# Core.net
KiCad netlist of a schematic drawn in Altium Designer
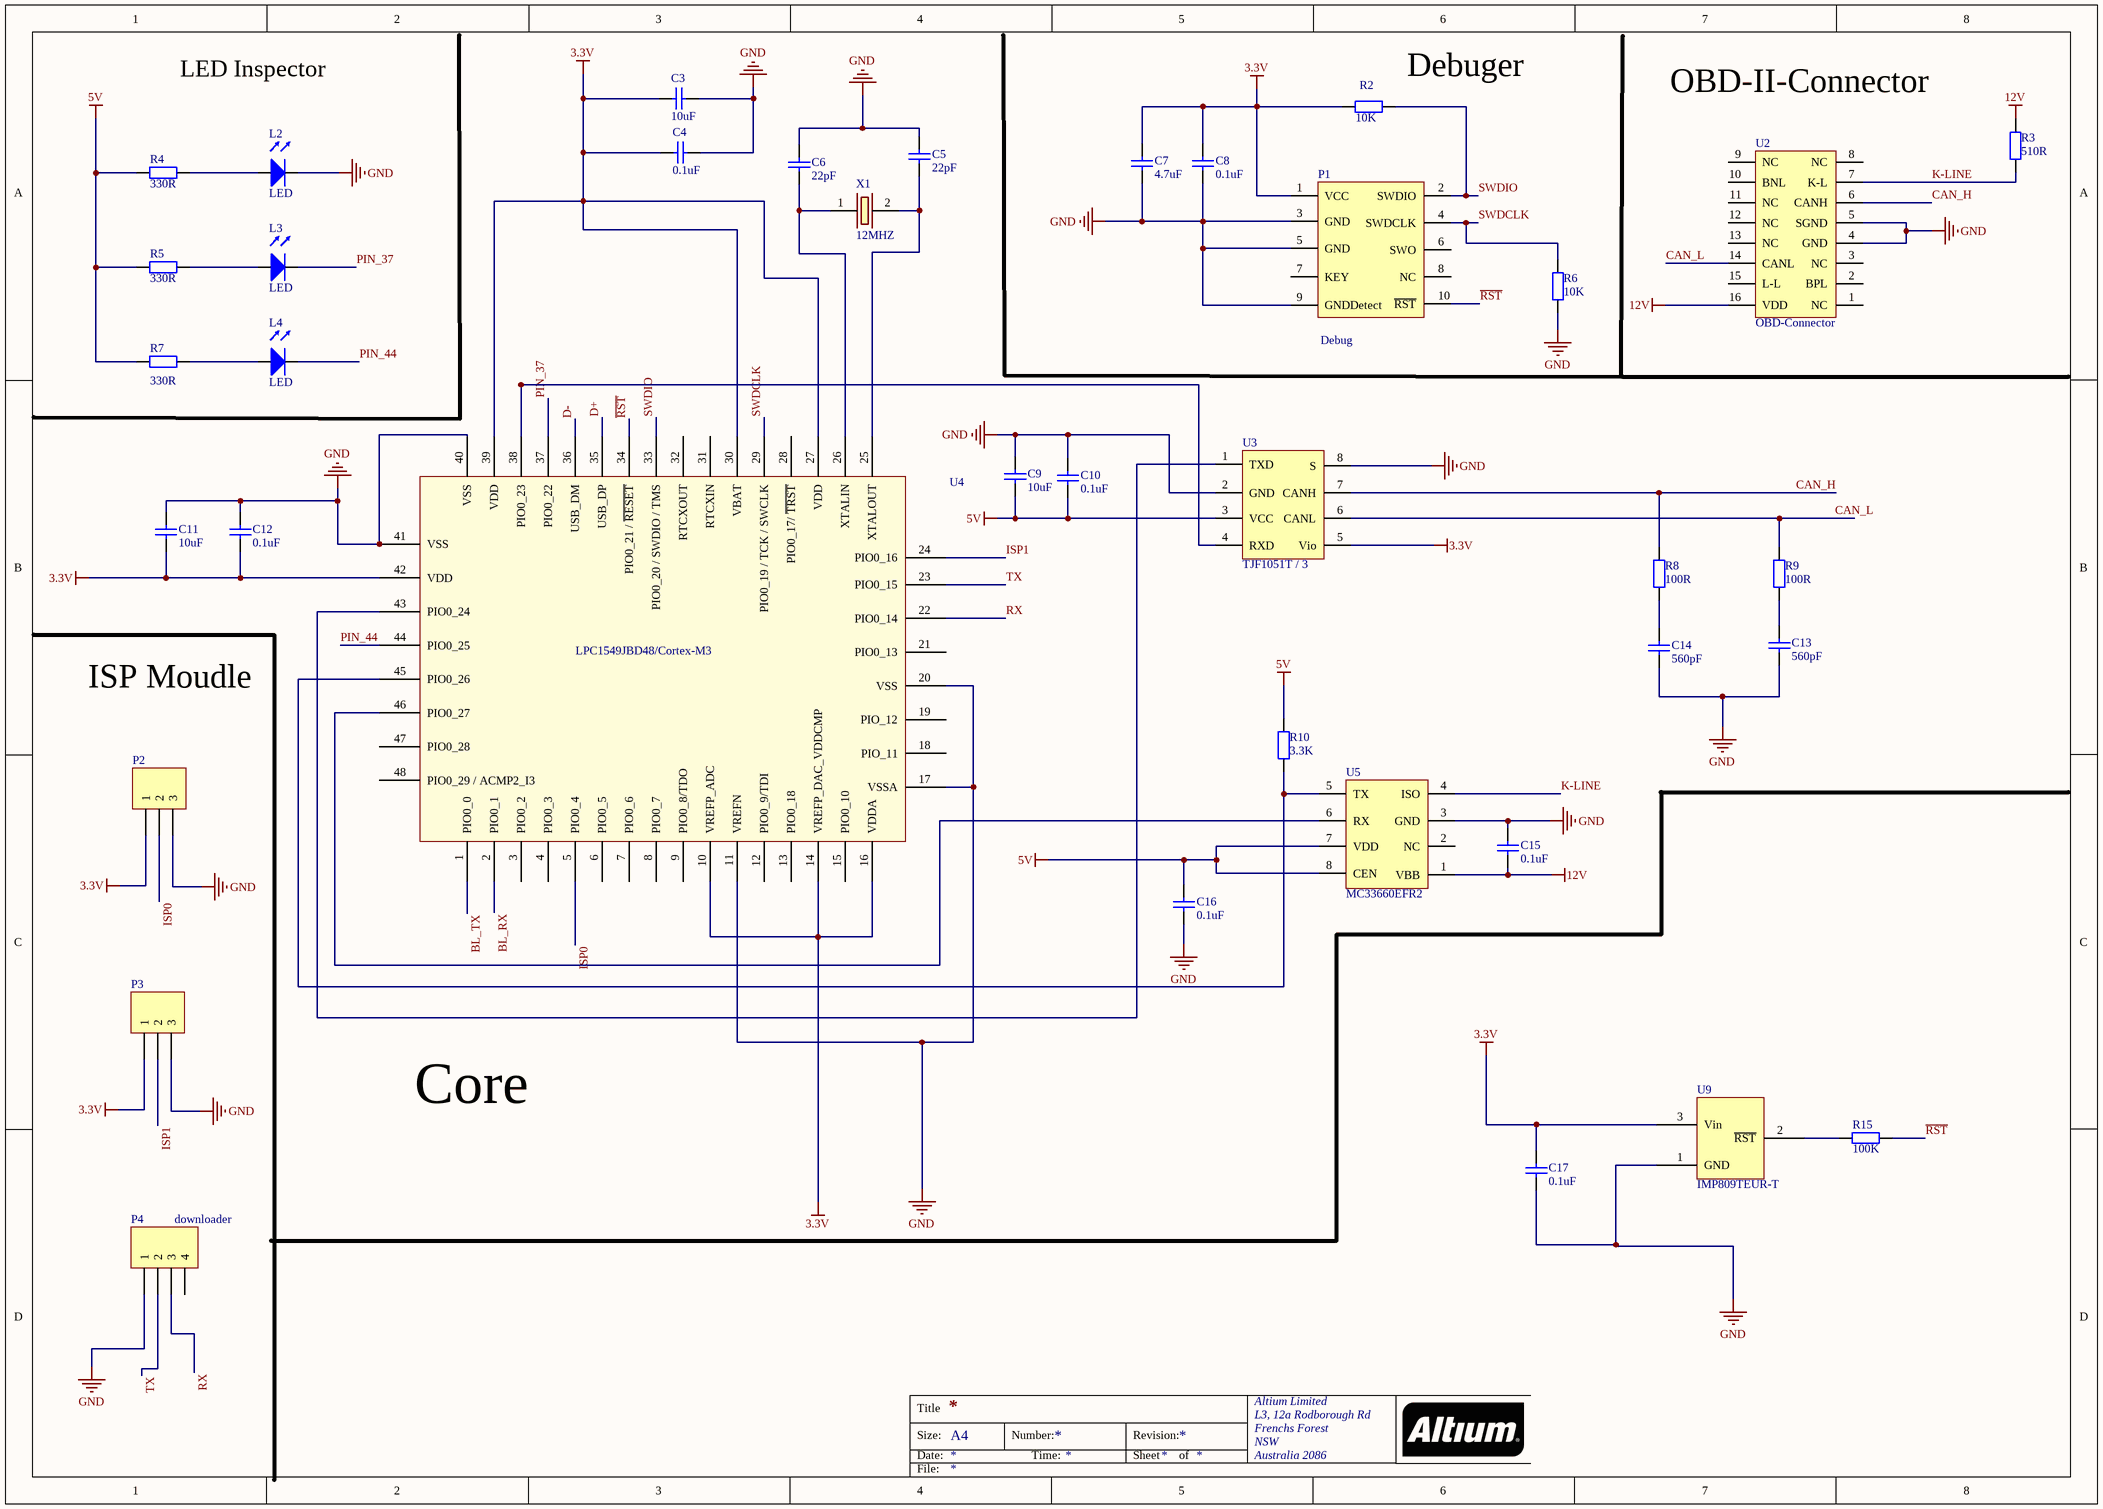
[diagram p0: Core.SchDoc]

(export (version "E")
  (design (tool "Eeschema 10.0.6"))
  (components
    (comp (ref "C3")
      (value "10uF")
      (footprint "0603")
      (description "ceramic")
      (libsource (lib "ToponLib") (part "Cap1"))
    )
    (comp (ref "C4")
      (value "0.1uF")
      (footprint "0603")
      (description "ceramic")
      (libsource (lib "ToponLib") (part "Cap1"))
    )
    (comp (ref "C5")
      (value "22pF")
      (footprint "0603")
      (description "ceramic")
      (libsource (lib "ToponLib") (part "Cap1"))
    )
    (comp (ref "C6")
      (value "22pF")
      (footprint "0603")
      (description "ceramic")
      (libsource (lib "ToponLib") (part "Cap1"))
    )
    (comp (ref "C7")
      (value "4.7uF")
      (footprint "0603")
      (description "ceramic")
      (libsource (lib "ToponLib") (part "Cap1"))
    )
    (comp (ref "C8")
      (value "0.1uF")
      (footprint "0603")
      (description "ceramic")
      (libsource (lib "ToponLib") (part "Cap1"))
    )
    (comp (ref "C9")
      (value "10uF")
      (footprint "0603")
      (description "ceramic")
      (libsource (lib "ToponLib") (part "Cap1"))
    )
    (comp (ref "C10")
      (value "0.1uF")
      (footprint "0603")
      (description "ceramic")
      (libsource (lib "ToponLib") (part "Cap1"))
    )
    (comp (ref "C11")
      (value "10uF")
      (footprint "0603")
      (description "ceramic")
      (libsource (lib "ToponLib") (part "Cap1"))
    )
    (comp (ref "C12")
      (value "0.1uF")
      (footprint "0603")
      (description "ceramic")
      (libsource (lib "ToponLib") (part "Cap1"))
    )
    (comp (ref "C13")
      (value "560pF")
      (footprint "0603")
      (description "ceramic")
      (libsource (lib "ToponLib") (part "Cap1"))
    )
    (comp (ref "C14")
      (value "560pF")
      (footprint "0603")
      (description "ceramic")
      (libsource (lib "ToponLib") (part "Cap1"))
    )
    (comp (ref "C15")
      (value "0.1uF")
      (footprint "0603")
      (description "ceramic")
      (libsource (lib "ToponLib") (part "Cap1"))
    )
    (comp (ref "C16")
      (value "0.1uF")
      (footprint "0603")
      (description "ceramic")
      (libsource (lib "ToponLib") (part "Cap1"))
    )
    (comp (ref "C17")
      (value "0.1uF")
      (footprint "0603")
      (description "ceramic")
      (libsource (lib "ToponLib") (part "Cap1"))
    )
    (comp (ref "L2") (value "LED") (footprint "0805") (libsource (lib "ToponLib") (part "LED")))
    (comp (ref "L3") (value "LED") (footprint "0805") (libsource (lib "ToponLib") (part "LED")))
    (comp (ref "L4") (value "LED") (footprint "0805") (libsource (lib "ToponLib") (part "LED")))
    (comp (ref "P1")
      (value "Debug")
      (footprint "JATG_10pin")
      (libsource (lib "ToponLib") (part "JTAG_10Pin"))
    )
    (comp (ref "P2")
      (value "~")
      (footprint "HDR1X3")
      (description "Header, 3-Pin")
      (fields (field (name "PUBLISHER") "Altium Limited"))
      (libsource (lib "Miscellaneous Connectors") (part "Header 3"))
    )
    (comp (ref "P3")
      (value "~")
      (footprint "HDR1X3")
      (description "Header, 3-Pin")
      (fields (field (name "PUBLISHER") "Altium Limited"))
      (libsource (lib "Miscellaneous Connectors") (part "Header 3"))
    )
    (comp (ref "P4")
      (value "downloader")
      (footprint "HDR1X4")
      (description "Header, 4-Pin")
      (fields (field (name "PUBLISHER") "Altium Limited"))
      (libsource (lib "Miscellaneous Connectors") (part "Header 4"))
    )
    (comp (ref "R2") (value "10K") (footprint "0603") (libsource (lib "ToponLib") (part "Res")))
    (comp (ref "R3") (value "510R") (footprint "0603") (libsource (lib "") (part "Res_1")))
    (comp (ref "R4") (value "330R") (footprint "0603") (libsource (lib "ToponLib") (part "Res")))
    (comp (ref "R5") (value "330R") (footprint "0603") (libsource (lib "ToponLib") (part "Res")))
    (comp (ref "R6") (value "10K") (footprint "0603") (libsource (lib "") (part "Res_1")))
    (comp (ref "R7") (value "330R") (footprint "0603") (libsource (lib "ToponLib") (part "Res")))
    (comp (ref "R8") (value "100R") (footprint "0603") (libsource (lib "") (part "Res_1")))
    (comp (ref "R9") (value "100R") (footprint "0603") (libsource (lib "") (part "Res_1")))
    (comp (ref "R10") (value "3.3K") (footprint "0603") (libsource (lib "") (part "Res_1")))
    (comp (ref "R15") (value "100K") (footprint "0603") (libsource (lib "") (part "Res_2")))
    (comp (ref "U2")
      (value "OBD-Connector")
      (footprint "OBD-MaleConnector")
      (libsource (lib "ToponLib") (part "OBD-MaleHead"))
    )
    (comp (ref "U3")
      (value "TJF1051T / 3")
      (footprint "TJF1051")
      (libsource (lib "ToponLib") (part "TJF1051T / 3"))
    )
    (comp (ref "U4")
      (value "LPC1549")
      (footprint "LPC1549JBD48")
      (libsource (lib "ToponLib") (part "LPC1549JBD48"))
    )
    (comp (ref "U5")
      (value "MC33660EFR2")
      (footprint "SOP-8")
      (libsource (lib "ToponLib") (part "MC33660EFR2"))
    )
    (comp (ref "U9")
      (value "IMP809TEUR-T")
      (footprint "SOT23-3")
      (libsource (lib "ToponLib") (part "IMP809TEUR-T"))
    )
    (comp (ref "X1") (value "12MHZ") (footprint "12Mhz-DFN") (libsource (lib "ToponLib") (part "OSC")))
  )
  (nets
    (net (code "1") (name "/BL_RX") (class "Default")
      (node (ref "U4") (pin "2") (pinfunction "PIO0_1_2") (pintype "passive"))
    )
    (net (code "2") (name "/BL_TX") (class "Default")
      (node (ref "U4") (pin "1") (pinfunction "PIO0_0_1") (pintype "passive"))
    )
    (net (code "3") (name "/CAN_H") (class "Default")
      (node (ref "R8") (pin "2") (pinfunction "2_2") (pintype "passive"))
      (node (ref "U2") (pin "6") (pinfunction "CANH_6") (pintype "passive"))
      (node (ref "U3") (pin "7") (pinfunction "CANH_7") (pintype "passive"))
    )
    (net (code "4") (name "/CAN_L") (class "Default")
      (node (ref "R9") (pin "2") (pinfunction "2_2") (pintype "passive"))
      (node (ref "U2") (pin "14") (pinfunction "CANL_14") (pintype "passive"))
      (node (ref "U3") (pin "6") (pinfunction "CANL_6") (pintype "passive"))
    )
    (net (code "5") (name "/D+") (class "Default")
      (node (ref "U4") (pin "35") (pinfunction "USB_DP_35") (pintype "passive"))
    )
    (net (code "6") (name "/D-") (class "Default")
      (node (ref "U4") (pin "36") (pinfunction "USB_DM_36") (pintype "passive"))
    )
    (net (code "7") (name "/ISP0") (class "Default")
      (node (ref "P2") (pin "2") (pinfunction "2_2") (pintype "passive"))
      (node (ref "U4") (pin "5") (pinfunction "PIO0_4_5") (pintype "passive"))
    )
    (net (code "8") (name "/ISP1") (class "Default")
      (node (ref "P3") (pin "2") (pinfunction "2_2") (pintype "passive"))
      (node (ref "U4") (pin "24") (pinfunction "PIO0_16_24") (pintype "passive"))
    )
    (net (code "9") (name "/K-LINE") (class "Default")
      (node (ref "R3") (pin "1") (pinfunction "1_1") (pintype "passive"))
      (node (ref "U2") (pin "7") (pinfunction "K-L_7") (pintype "passive"))
      (node (ref "U5") (pin "4") (pinfunction "ISO_4") (pintype "passive"))
    )
    (net (code "10") (name "/PIN_37") (class "Default")
      (node (ref "L3") (pin "2") (pinfunction "K_2") (pintype "passive"))
      (node (ref "U4") (pin "37") (pinfunction "PIO0_22_37") (pintype "passive"))
    )
    (net (code "11") (name "/PIN_44") (class "Default")
      (node (ref "L4") (pin "2") (pinfunction "K_2") (pintype "passive"))
      (node (ref "U4") (pin "44") (pinfunction "PIO0_25_44") (pintype "passive"))
    )
    (net (code "12") (name "/RX") (class "Default")
      (node (ref "P4") (pin "3") (pinfunction "3_3") (pintype "passive"))
      (node (ref "U4") (pin "22") (pinfunction "PIO0_14_22") (pintype "passive"))
    )
    (net (code "13") (name "/SWDCLK") (class "Default")
      (node (ref "P1") (pin "4") (pinfunction "SWDCLK_4") (pintype "passive"))
      (node (ref "R6") (pin "2") (pinfunction "2_2") (pintype "passive"))
      (node (ref "U4") (pin "29") (pinfunction "PIO0_19_/_TCK_/_SWCLK_29") (pintype "passive"))
    )
    (net (code "14") (name "/SWDIO") (class "Default")
      (node (ref "P1") (pin "2") (pinfunction "SWDIO_2") (pintype "passive"))
      (node (ref "R2") (pin "2") (pinfunction "2_2") (pintype "passive"))
      (node (ref "U4") (pin "33") (pinfunction "PIO0_20_/_SWDIO_/_TMS_33") (pintype "passive"))
    )
    (net (code "15") (name "/TX") (class "Default")
      (node (ref "P4") (pin "2") (pinfunction "2_2") (pintype "passive"))
      (node (ref "U4") (pin "23") (pinfunction "PIO0_15_23") (pintype "passive"))
    )
    (net (code "16") (name "/~{RST}") (class "Default")
      (node (ref "P1") (pin "10") (pinfunction "~{RST}_10") (pintype "passive"))
      (node (ref "R15") (pin "1") (pinfunction "1_1") (pintype "passive"))
      (node (ref "U4") (pin "34") (pinfunction "PIO0_21_/_~{RESET}_34") (pintype "passive"))
    )
    (net (code "17") (name "3.3V") (class "Default")
      (node (ref "C11") (pin "1") (pinfunction "1_1") (pintype "passive"))
      (node (ref "C12") (pin "1") (pinfunction "1_1") (pintype "passive"))
      (node (ref "C17") (pin "2") (pinfunction "2_2") (pintype "passive"))
      (node (ref "C3") (pin "2") (pinfunction "2_2") (pintype "passive"))
      (node (ref "C4") (pin "2") (pinfunction "2_2") (pintype "passive"))
      (node (ref "C7") (pin "2") (pinfunction "2_2") (pintype "passive"))
      (node (ref "C8") (pin "2") (pinfunction "2_2") (pintype "passive"))
      (node (ref "P1") (pin "1") (pinfunction "VCC_1") (pintype "passive"))
      (node (ref "P2") (pin "1") (pinfunction "1_1") (pintype "passive"))
      (node (ref "P3") (pin "1") (pinfunction "1_1") (pintype "passive"))
      (node (ref "R2") (pin "1") (pinfunction "1_1") (pintype "passive"))
      (node (ref "U3") (pin "5") (pinfunction "Vio_5") (pintype "passive"))
      (node (ref "U4") (pin "10") (pinfunction "VREFP_ADC_10") (pintype "passive"))
      (node (ref "U4") (pin "14") (pinfunction "VREFP_DAC_VDDCMP_14") (pintype "passive"))
      (node (ref "U4") (pin "16") (pinfunction "VDDA_16") (pintype "passive"))
      (node (ref "U4") (pin "27") (pinfunction "VDD_27") (pintype "passive"))
      (node (ref "U4") (pin "30") (pinfunction "VBAT_30") (pintype "passive"))
      (node (ref "U4") (pin "39") (pinfunction "VDD_39") (pintype "passive"))
      (node (ref "U4") (pin "42") (pinfunction "VDD_42") (pintype "passive"))
      (node (ref "U9") (pin "3") (pinfunction "Vin_3") (pintype "passive"))
    )
    (net (code "18") (name "5V") (class "Default")
      (node (ref "C10") (pin "1") (pinfunction "1_1") (pintype "passive"))
      (node (ref "C16") (pin "2") (pinfunction "2_2") (pintype "passive"))
      (node (ref "C9") (pin "1") (pinfunction "1_1") (pintype "passive"))
      (node (ref "R10") (pin "2") (pinfunction "2_2") (pintype "passive"))
      (node (ref "R4") (pin "1") (pinfunction "1_1") (pintype "passive"))
      (node (ref "R5") (pin "1") (pinfunction "1_1") (pintype "passive"))
      (node (ref "R7") (pin "1") (pinfunction "1_1") (pintype "passive"))
      (node (ref "U3") (pin "3") (pinfunction "VCC_3") (pintype "passive"))
      (node (ref "U5") (pin "7") (pinfunction "VDD_7") (pintype "passive"))
      (node (ref "U5") (pin "8") (pinfunction "CEN_8") (pintype "passive"))
    )
    (net (code "19") (name "12V") (class "Default")
      (node (ref "C15") (pin "1") (pinfunction "1_1") (pintype "passive"))
      (node (ref "R3") (pin "2") (pinfunction "2_2") (pintype "passive"))
      (node (ref "U2") (pin "16") (pinfunction "VDD_16") (pintype "passive"))
      (node (ref "U5") (pin "1") (pinfunction "VBB_1") (pintype "passive"))
    )
    (net (code "20") (name "GND") (class "Default")
      (node (ref "C10") (pin "2") (pinfunction "2_2") (pintype "passive"))
      (node (ref "C11") (pin "2") (pinfunction "2_2") (pintype "passive"))
      (node (ref "C12") (pin "2") (pinfunction "2_2") (pintype "passive"))
      (node (ref "C13") (pin "1") (pinfunction "1_1") (pintype "passive"))
      (node (ref "C14") (pin "1") (pinfunction "1_1") (pintype "passive"))
      (node (ref "C15") (pin "2") (pinfunction "2_2") (pintype "passive"))
      (node (ref "C16") (pin "1") (pinfunction "1_1") (pintype "passive"))
      (node (ref "C17") (pin "1") (pinfunction "1_1") (pintype "passive"))
      (node (ref "C3") (pin "1") (pinfunction "1_1") (pintype "passive"))
      (node (ref "C4") (pin "1") (pinfunction "1_1") (pintype "passive"))
      (node (ref "C5") (pin "2") (pinfunction "2_2") (pintype "passive"))
      (node (ref "C6") (pin "2") (pinfunction "2_2") (pintype "passive"))
      (node (ref "C7") (pin "1") (pinfunction "1_1") (pintype "passive"))
      (node (ref "C8") (pin "1") (pinfunction "1_1") (pintype "passive"))
      (node (ref "C9") (pin "2") (pinfunction "2_2") (pintype "passive"))
      (node (ref "L2") (pin "2") (pinfunction "K_2") (pintype "passive"))
      (node (ref "P1") (pin "3") (pinfunction "GND_3") (pintype "passive"))
      (node (ref "P1") (pin "5") (pinfunction "GND_5") (pintype "passive"))
      (node (ref "P1") (pin "9") (pinfunction "GNDDetect_9") (pintype "passive"))
      (node (ref "P2") (pin "3") (pinfunction "3_3") (pintype "passive"))
      (node (ref "P3") (pin "3") (pinfunction "3_3") (pintype "passive"))
      (node (ref "P4") (pin "1") (pinfunction "1_1") (pintype "passive"))
      (node (ref "R6") (pin "1") (pinfunction "1_1") (pintype "passive"))
      (node (ref "U2") (pin "4") (pinfunction "GND_4") (pintype "passive"))
      (node (ref "U2") (pin "5") (pinfunction "SGND_5") (pintype "passive"))
      (node (ref "U3") (pin "2") (pinfunction "GND_2") (pintype "passive"))
      (node (ref "U3") (pin "8") (pinfunction "S_8") (pintype "passive"))
      (node (ref "U4") (pin "11") (pinfunction "VREFN_11") (pintype "passive"))
      (node (ref "U4") (pin "17") (pinfunction "VSSA_17") (pintype "passive"))
      (node (ref "U4") (pin "20") (pinfunction "VSS_20") (pintype "passive"))
      (node (ref "U4") (pin "40") (pinfunction "VSS_40") (pintype "passive"))
      (node (ref "U4") (pin "41") (pinfunction "VSS_41") (pintype "passive"))
      (node (ref "U5") (pin "3") (pinfunction "GND_3") (pintype "passive"))
      (node (ref "U9") (pin "1") (pinfunction "GND_1") (pintype "passive"))
    )
    (net (code "21") (name "Net-(C13-Pad2)") (class "Default")
      (node (ref "C13") (pin "2") (pinfunction "2_2") (pintype "passive"))
      (node (ref "R9") (pin "1") (pinfunction "1_1") (pintype "passive"))
    )
    (net (code "22") (name "Net-(C14-Pad2)") (class "Default")
      (node (ref "C14") (pin "2") (pinfunction "2_2") (pintype "passive"))
      (node (ref "R8") (pin "1") (pinfunction "1_1") (pintype "passive"))
    )
    (net (code "23") (name "Net-(L2-A)") (class "Default")
      (node (ref "L2") (pin "1") (pinfunction "A_1") (pintype "passive"))
      (node (ref "R4") (pin "2") (pinfunction "2_2") (pintype "passive"))
    )
    (net (code "24") (name "Net-(L3-A)") (class "Default")
      (node (ref "L3") (pin "1") (pinfunction "A_1") (pintype "passive"))
      (node (ref "R5") (pin "2") (pinfunction "2_2") (pintype "passive"))
    )
    (net (code "25") (name "Net-(L4-A)") (class "Default")
      (node (ref "L4") (pin "1") (pinfunction "A_1") (pintype "passive"))
      (node (ref "R7") (pin "2") (pinfunction "2_2") (pintype "passive"))
    )
    (net (code "26") (name "Net-(U3-RXD)") (class "Default")
      (node (ref "U3") (pin "4") (pinfunction "RXD_4") (pintype "passive"))
      (node (ref "U4") (pin "38") (pinfunction "PIO0_23_38") (pintype "passive"))
    )
    (net (code "27") (name "Net-(U3-TXD)") (class "Default")
      (node (ref "U3") (pin "1") (pinfunction "TXD_1") (pintype "passive"))
      (node (ref "U4") (pin "43") (pinfunction "PIO0_24_43") (pintype "passive"))
    )
    (net (code "28") (name "Net-(U4-PIO0_26)") (class "Default")
      (node (ref "R10") (pin "1") (pinfunction "1_1") (pintype "passive"))
      (node (ref "U4") (pin "45") (pinfunction "PIO0_26_45") (pintype "passive"))
      (node (ref "U5") (pin "5") (pinfunction "TX_5") (pintype "passive"))
    )
    (net (code "29") (name "Net-(U4-PIO0_27)") (class "Default")
      (node (ref "U4") (pin "46") (pinfunction "PIO0_27_46") (pintype "passive"))
      (node (ref "U5") (pin "6") (pinfunction "RX_6") (pintype "passive"))
    )
    (net (code "30") (name "Net-(U4-XTALIN)") (class "Default")
      (node (ref "C6") (pin "1") (pinfunction "1_1") (pintype "passive"))
      (node (ref "U4") (pin "26") (pinfunction "XTALIN_26") (pintype "passive"))
      (node (ref "X1") (pin "1") (pinfunction "1_1") (pintype "passive"))
    )
    (net (code "31") (name "Net-(U4-XTALOUT)") (class "Default")
      (node (ref "C5") (pin "1") (pinfunction "1_1") (pintype "passive"))
      (node (ref "U4") (pin "25") (pinfunction "XTALOUT_25") (pintype "passive"))
      (node (ref "X1") (pin "2") (pinfunction "2_2") (pintype "passive"))
    )
    (net (code "32") (name "Net-(U9-~{RST})") (class "Default")
      (node (ref "R15") (pin "2") (pinfunction "2_2") (pintype "passive"))
      (node (ref "U9") (pin "2") (pinfunction "~{RST}_2") (pintype "passive"))
    )
    (net (code "33") (name "unconnected-(P1-KEY-Pad7)") (class "Default")
      (node (ref "P1") (pin "7") (pinfunction "KEY_7") (pintype "passive"))
    )
    (net (code "34") (name "unconnected-(P1-NC-Pad8)") (class "Default")
      (node (ref "P1") (pin "8") (pinfunction "NC_8") (pintype "passive"))
    )
    (net (code "35") (name "unconnected-(P1-SWO-Pad6)") (class "Default")
      (node (ref "P1") (pin "6") (pinfunction "SWO_6") (pintype "passive"))
    )
    (net (code "36") (name "unconnected-(P4-Pad4)") (class "Default")
      (node (ref "P4") (pin "4") (pinfunction "4_4") (pintype "passive"))
    )
    (net (code "37") (name "unconnected-(U2-BNL-Pad10)") (class "Default")
      (node (ref "U2") (pin "10") (pinfunction "BNL_10") (pintype "passive"))
    )
    (net (code "38") (name "unconnected-(U2-BPL-Pad2)") (class "Default")
      (node (ref "U2") (pin "2") (pinfunction "BPL_2") (pintype "passive"))
    )
    (net (code "39") (name "unconnected-(U2-L-L-Pad15)") (class "Default")
      (node (ref "U2") (pin "15") (pinfunction "L-L_15") (pintype "passive"))
    )
    (net (code "40") (name "unconnected-(U2-NC-Pad1)") (class "Default")
      (node (ref "U2") (pin "1") (pinfunction "NC_1") (pintype "passive"))
    )
    (net (code "41") (name "unconnected-(U2-NC-Pad3)") (class "Default")
      (node (ref "U2") (pin "3") (pinfunction "NC_3") (pintype "passive"))
    )
    (net (code "42") (name "unconnected-(U2-NC-Pad8)") (class "Default")
      (node (ref "U2") (pin "8") (pinfunction "NC_8") (pintype "passive"))
    )
    (net (code "43") (name "unconnected-(U2-NC-Pad9)") (class "Default")
      (node (ref "U2") (pin "9") (pinfunction "NC_9") (pintype "passive"))
    )
    (net (code "44") (name "unconnected-(U2-NC-Pad11)") (class "Default")
      (node (ref "U2") (pin "11") (pinfunction "NC_11") (pintype "passive"))
    )
    (net (code "45") (name "unconnected-(U2-NC-Pad12)") (class "Default")
      (node (ref "U2") (pin "12") (pinfunction "NC_12") (pintype "passive"))
    )
    (net (code "46") (name "unconnected-(U2-NC-Pad13)") (class "Default")
      (node (ref "U2") (pin "13") (pinfunction "NC_13") (pintype "passive"))
    )
    (net (code "47") (name "unconnected-(U4-PIO0_2-Pad3)") (class "Default")
      (node (ref "U4") (pin "3") (pinfunction "PIO0_2_3") (pintype "passive"))
    )
    (net (code "48") (name "unconnected-(U4-PIO0_3-Pad4)") (class "Default")
      (node (ref "U4") (pin "4") (pinfunction "PIO0_3_4") (pintype "passive"))
    )
    (net (code "49") (name "unconnected-(U4-PIO0_5-Pad6)") (class "Default")
      (node (ref "U4") (pin "6") (pinfunction "PIO0_5_6") (pintype "passive"))
    )
    (net (code "50") (name "unconnected-(U4-PIO0_6-Pad7)") (class "Default")
      (node (ref "U4") (pin "7") (pinfunction "PIO0_6_7") (pintype "passive"))
    )
    (net (code "51") (name "unconnected-(U4-PIO0_7-Pad8)") (class "Default")
      (node (ref "U4") (pin "8") (pinfunction "PIO0_7_8") (pintype "passive"))
    )
    (net (code "52") (name "unconnected-(U4-PIO0_8{slash}TDO-Pad9)") (class "Default")
      (node (ref "U4") (pin "9") (pinfunction "PIO0_8/TDO_9") (pintype "passive"))
    )
    (net (code "53") (name "unconnected-(U4-PIO0_9{slash}TDI-Pad12)") (class "Default")
      (node (ref "U4") (pin "12") (pinfunction "PIO0_9/TDI_12") (pintype "passive"))
    )
    (net (code "54") (name "unconnected-(U4-PIO0_10-Pad15)") (class "Default")
      (node (ref "U4") (pin "15") (pinfunction "PIO0_10_15") (pintype "passive"))
    )
    (net (code "55") (name "unconnected-(U4-PIO0_13-Pad21)") (class "Default")
      (node (ref "U4") (pin "21") (pinfunction "PIO0_13_21") (pintype "passive"))
    )
    (net (code "56") (name "unconnected-(U4-PIO0_17{slash}_~{TRST}-Pad28)") (class "Default")
      (node (ref "U4") (pin "28") (pinfunction "PIO0_17/_~{TRST}_28") (pintype "passive"))
    )
    (net (code "57") (name "unconnected-(U4-PIO0_18-Pad13)") (class "Default")
      (node (ref "U4") (pin "13") (pinfunction "PIO0_18_13") (pintype "passive"))
    )
    (net (code "58") (name "unconnected-(U4-PIO0_28-Pad47)") (class "Default")
      (node (ref "U4") (pin "47") (pinfunction "PIO0_28_47") (pintype "passive"))
    )
    (net (code "59") (name "unconnected-(U4-PIO0_29_{slash}_ACMP2_I3-Pad48)") (class "Default")
      (node (ref "U4") (pin "48") (pinfunction "PIO0_29_/_ACMP2_I3_48") (pintype "passive"))
    )
    (net (code "60") (name "unconnected-(U4-PIO_11-Pad18)") (class "Default")
      (node (ref "U4") (pin "18") (pinfunction "PIO_11_18") (pintype "passive"))
    )
    (net (code "61") (name "unconnected-(U4-PIO_12-Pad19)") (class "Default")
      (node (ref "U4") (pin "19") (pinfunction "PIO_12_19") (pintype "passive"))
    )
    (net (code "62") (name "unconnected-(U4-RTCXIN-Pad31)") (class "Default")
      (node (ref "U4") (pin "31") (pinfunction "RTCXIN_31") (pintype "passive"))
    )
    (net (code "63") (name "unconnected-(U4-RTCXOUT-Pad32)") (class "Default")
      (node (ref "U4") (pin "32") (pinfunction "RTCXOUT_32") (pintype "passive"))
    )
    (net (code "64") (name "unconnected-(U5-NC-Pad2)") (class "Default")
      (node (ref "U5") (pin "2") (pinfunction "NC_2") (pintype "passive"))
    )
  )
)
